# TRANSMITTER.net
KiCad netlist of a schematic drawn in EAGLE
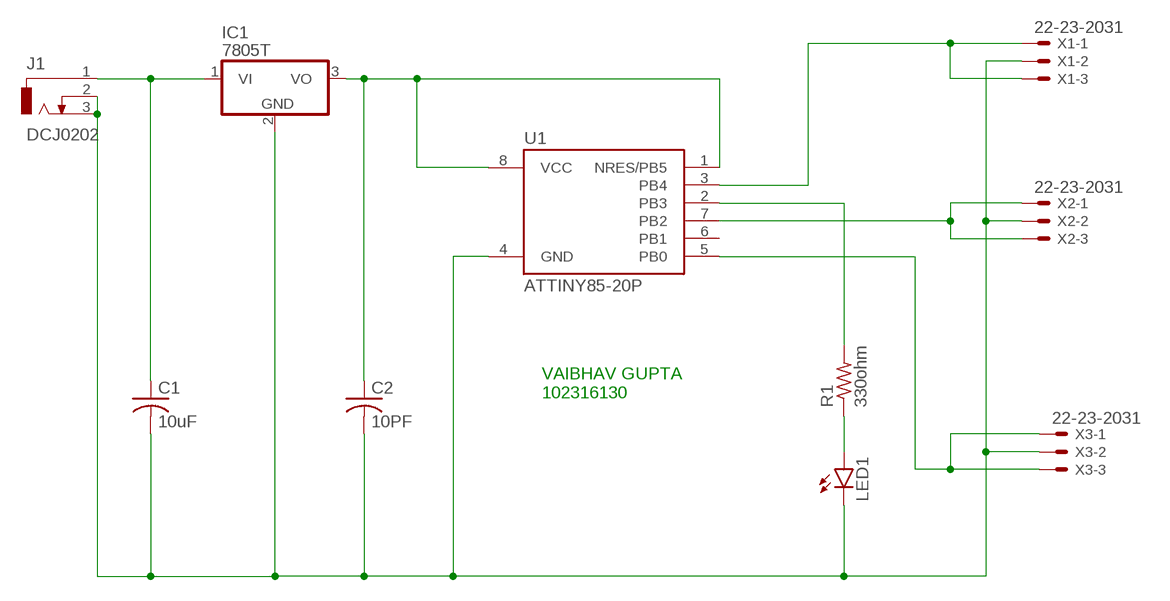
[diagram p0: schematic, sheet 1]

(export (version "E")
  (design (tool "Eeschema 10.0.6"))
  (components
    (comp (ref "C1")
      (value "10uF")
      (footprint "eagle-import:C025-024X044")
      (libsource (lib "eagle-import") (part "C-US025-024X044"))
    )
    (comp (ref "C2")
      (value "10PF")
      (footprint "eagle-import:C025-024X044")
      (libsource (lib "eagle-import") (part "C-US025-024X044"))
    )
    (comp (ref "IC1")
      (value "7805T")
      (footprint "eagle-import:TO220H")
      (libsource (lib "eagle-import") (part "78T05"))
    )
    (comp (ref "J1")
      (value "DCJ0202")
      (footprint "eagle-import:DCJ0202")
      (libsource (lib "eagle-import") (part "DCJ0202"))
    )
    (comp (ref "LED1")
      (value "LED3MM")
      (footprint "eagle-import:LED3MM")
      (libsource (lib "eagle-import") (part "LED3MM"))
    )
    (comp (ref "R1")
      (value "330ohm")
      (footprint "eagle-import:0207_5V")
      (libsource (lib "eagle-import") (part "R-US_0207/5V"))
    )
    (comp (ref "U1")
      (value "ATTINY85-20P")
      (footprint "eagle-import:PDIP08_300MIL")
      (libsource (lib "eagle-import") (part "ATTINY85P-20"))
    )
    (comp (ref "X1")
      (value "22-23-2031")
      (footprint "eagle-import:22-23-2031")
      (fields (field (name "MF") "MOLEX"))
      (libsource (lib "eagle-import") (part "22-23-2031"))
    )
    (comp (ref "X2")
      (value "22-23-2031")
      (footprint "eagle-import:22-23-2031")
      (fields (field (name "MF") "MOLEX"))
      (libsource (lib "eagle-import") (part "22-23-2031"))
    )
    (comp (ref "X3")
      (value "22-23-2031")
      (footprint "eagle-import:22-23-2031")
      (fields (field (name "MF") "MOLEX"))
      (libsource (lib "eagle-import") (part "22-23-2031"))
    )
  )
  (nets
    (net (code "1") (name "Net-(IC1-GND)") (class "Default")
      (node (ref "C1") (pin "2") (pinfunction "2_2") (pintype "passive"))
      (node (ref "C2") (pin "2") (pinfunction "2_2") (pintype "passive"))
      (node (ref "IC1") (pin "2") (pinfunction "GND_2") (pintype "passive"))
      (node (ref "J1") (pin "2") (pinfunction "2_2") (pintype "passive"))
      (node (ref "J1") (pin "3") (pinfunction "3_3") (pintype "passive"))
      (node (ref "LED1") (pin "K") (pinfunction "C_K") (pintype "passive"))
      (node (ref "U1") (pin "4") (pinfunction "GND_4") (pintype "power_in"))
      (node (ref "X1") (pin "2") (pinfunction "S_2") (pintype "passive"))
      (node (ref "X2") (pin "2") (pinfunction "S_2") (pintype "passive"))
      (node (ref "X3") (pin "2") (pinfunction "S_2") (pintype "passive"))
    )
    (net (code "2") (name "Net-(IC1-VI)") (class "Default")
      (node (ref "C1") (pin "1") (pinfunction "1_1") (pintype "passive"))
      (node (ref "IC1") (pin "1") (pinfunction "VI_1") (pintype "input"))
      (node (ref "J1") (pin "1") (pinfunction "1_1") (pintype "passive"))
    )
    (net (code "3") (name "Net-(IC1-VO)") (class "Default")
      (node (ref "C2") (pin "1") (pinfunction "1_1") (pintype "passive"))
      (node (ref "IC1") (pin "3") (pinfunction "VO_3") (pintype "passive"))
      (node (ref "U1") (pin "1") (pinfunction "NRES/PB5_1") (pintype "bidirectional"))
      (node (ref "U1") (pin "8") (pinfunction "VCC_8") (pintype "power_in"))
    )
    (net (code "4") (name "Net-(LED1-PadA)") (class "Default")
      (node (ref "LED1") (pin "A") (pinfunction "A_A") (pintype "passive"))
      (node (ref "R1") (pin "1") (pinfunction "1_1") (pintype "passive"))
    )
    (net (code "5") (name "Net-(U1-PB0)") (class "Default")
      (node (ref "U1") (pin "5") (pinfunction "PB0_5") (pintype "bidirectional"))
      (node (ref "X3") (pin "1") (pinfunction "S_1") (pintype "passive"))
      (node (ref "X3") (pin "3") (pinfunction "S_3") (pintype "passive"))
    )
    (net (code "6") (name "Net-(U1-PB2)") (class "Default")
      (node (ref "U1") (pin "7") (pinfunction "PB2_7") (pintype "bidirectional"))
      (node (ref "X2") (pin "1") (pinfunction "S_1") (pintype "passive"))
      (node (ref "X2") (pin "3") (pinfunction "S_3") (pintype "passive"))
    )
    (net (code "7") (name "Net-(U1-PB3)") (class "Default")
      (node (ref "R1") (pin "2") (pinfunction "2_2") (pintype "passive"))
      (node (ref "U1") (pin "2") (pinfunction "PB3_2") (pintype "bidirectional"))
    )
    (net (code "8") (name "Net-(U1-PB4)") (class "Default")
      (node (ref "U1") (pin "3") (pinfunction "PB4_3") (pintype "bidirectional"))
      (node (ref "X1") (pin "1") (pinfunction "S_1") (pintype "passive"))
      (node (ref "X1") (pin "3") (pinfunction "S_3") (pintype "passive"))
    )
    (net (code "9") (name "unconnected-(U1-PB1-Pad6)") (class "Default")
      (node (ref "U1") (pin "6") (pinfunction "PB1_6") (pintype "bidirectional"))
    )
  )
)
